# boost.net
KiCad netlist of a schematic drawn in Altium Designer
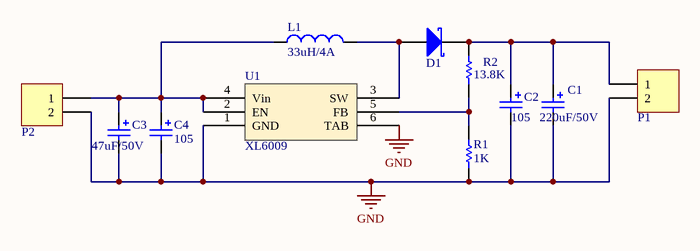
[diagram p0: boost.SchDoc]

(export (version "E")
  (design (tool "Eeschema 10.0.6"))
  (components
    (comp (ref "C1")
      (value "220uF/50V")
      (footprint "CAP ALU SIZE B")
      (description "Polarized Capacitor (Radial)")
      (fields (field (name "Comment") "Cap Pol SMD"))
      (libsource (lib "PIF_Library") (part "Cap Pol SMD"))
    )
    (comp (ref "C2")
      (value "105")
      (footprint "CAP ALU SIZE B")
      (description "Polarized Capacitor (Radial)")
      (fields (field (name "Comment") "Cap Pol SMD"))
      (libsource (lib "PIF_Library") (part "Cap Pol SMD"))
    )
    (comp (ref "C3")
      (value "47uF/50V")
      (footprint "CAP ALU SIZE B")
      (description "Polarized Capacitor (Radial)")
      (fields (field (name "Comment") "Cap Pol SMD"))
      (libsource (lib "PIF_Library") (part "Cap Pol SMD"))
    )
    (comp (ref "C4")
      (value "105")
      (footprint "CAP ALU SIZE B")
      (description "Polarized Capacitor (Radial)")
      (fields (field (name "Comment") "Cap Pol SMD"))
      (libsource (lib "PIF_Library") (part "Cap Pol SMD"))
    )
    (comp (ref "D1")
      (value "D Schottky")
      (footprint "SS34")
      (description "Schottky Diode")
      (fields (field (name "PUBLISHER") "Altium Limited"))
      (libsource (lib "PIF_Library") (part "D Schottky"))
    )
    (comp (ref "L1")
      (value "33uH/4A")
      (footprint "INDUCTOR 12.5x12.5")
      (description "Inductor")
      (libsource (lib "PIF_Library") (part "Inductor"))
    )
    (comp (ref "P1")
      (value "Header 2")
      (footprint "JP2")
      (description "Header, 2-Pin")
      (fields (field (name "PUBLISHER") "Altium Limited"))
      (libsource (lib "") (part "Header 2_1"))
    )
    (comp (ref "P2")
      (value "Header 2")
      (footprint "JP2")
      (description "Header, 2-Pin")
      (fields (field (name "PUBLISHER") "Altium Limited"))
      (libsource (lib "PIF_Library") (part "Header 2"))
    )
    (comp (ref "R1")
      (value "1K")
      (footprint "RES-SM-0603")
      (description "Resistor")
      (fields (field (name "Comment") "RESISTOR SMD"))
      (libsource (lib "PIF_Library") (part "RESISTOR SMD"))
    )
    (comp (ref "R2")
      (value "13.8K")
      (footprint "RES-SM-0603")
      (description "Resistor")
      (fields (field (name "Comment") "RESISTOR SMD"))
      (libsource (lib "PIF_Library") (part "RESISTOR SMD"))
    )
    (comp (ref "U1")
      (value "XL6009")
      (footprint "LM2596")
      (description "SMD")
      (libsource (lib "buck&boost") (part "XL6009"))
    )
  )
  (nets
    (net (code "1") (name "GND") (class "Default")
      (node (ref "C1") (pin "2") (pinfunction "2_2") (pintype "passive"))
      (node (ref "C2") (pin "2") (pinfunction "2_2") (pintype "passive"))
      (node (ref "C3") (pin "2") (pinfunction "2_2") (pintype "passive"))
      (node (ref "C4") (pin "2") (pinfunction "2_2") (pintype "passive"))
      (node (ref "P1") (pin "2") (pinfunction "2_2") (pintype "passive"))
      (node (ref "P2") (pin "2") (pinfunction "2_2") (pintype "passive"))
      (node (ref "R1") (pin "1") (pinfunction "1_1") (pintype "passive"))
      (node (ref "U1") (pin "1") (pinfunction "GND_1") (pintype "passive"))
      (node (ref "U1") (pin "6") (pinfunction "TAB_6") (pintype "passive"))
    )
    (net (code "2") (name "Net-(D1-A)") (class "Default")
      (node (ref "D1") (pin "1") (pinfunction "A_1") (pintype "passive"))
      (node (ref "L1") (pin "2") (pinfunction "2_2") (pintype "passive"))
      (node (ref "U1") (pin "3") (pinfunction "SW_3") (pintype "passive"))
    )
    (net (code "3") (name "Net-(D1-K)") (class "Default")
      (node (ref "C1") (pin "1") (pinfunction "1_1") (pintype "passive"))
      (node (ref "C2") (pin "1") (pinfunction "1_1") (pintype "passive"))
      (node (ref "D1") (pin "2") (pinfunction "K_2") (pintype "passive"))
      (node (ref "P1") (pin "1") (pinfunction "1_1") (pintype "passive"))
      (node (ref "R2") (pin "2") (pinfunction "2_2") (pintype "passive"))
    )
    (net (code "4") (name "Net-(U1-EN)") (class "Default")
      (node (ref "C3") (pin "1") (pinfunction "1_1") (pintype "passive"))
      (node (ref "C4") (pin "1") (pinfunction "1_1") (pintype "passive"))
      (node (ref "L1") (pin "1") (pinfunction "1_1") (pintype "passive"))
      (node (ref "P2") (pin "1") (pinfunction "1_1") (pintype "passive"))
      (node (ref "U1") (pin "2") (pinfunction "EN_2") (pintype "passive"))
      (node (ref "U1") (pin "4") (pinfunction "Vin_4") (pintype "passive"))
    )
    (net (code "5") (name "Net-(U1-FB)") (class "Default")
      (node (ref "R1") (pin "2") (pinfunction "2_2") (pintype "passive"))
      (node (ref "R2") (pin "1") (pinfunction "1_1") (pintype "passive"))
      (node (ref "U1") (pin "5") (pinfunction "FB_5") (pintype "passive"))
    )
  )
)
